# ArduinoUnoShield.net
KiCad netlist of a schematic drawn in Altium Designer
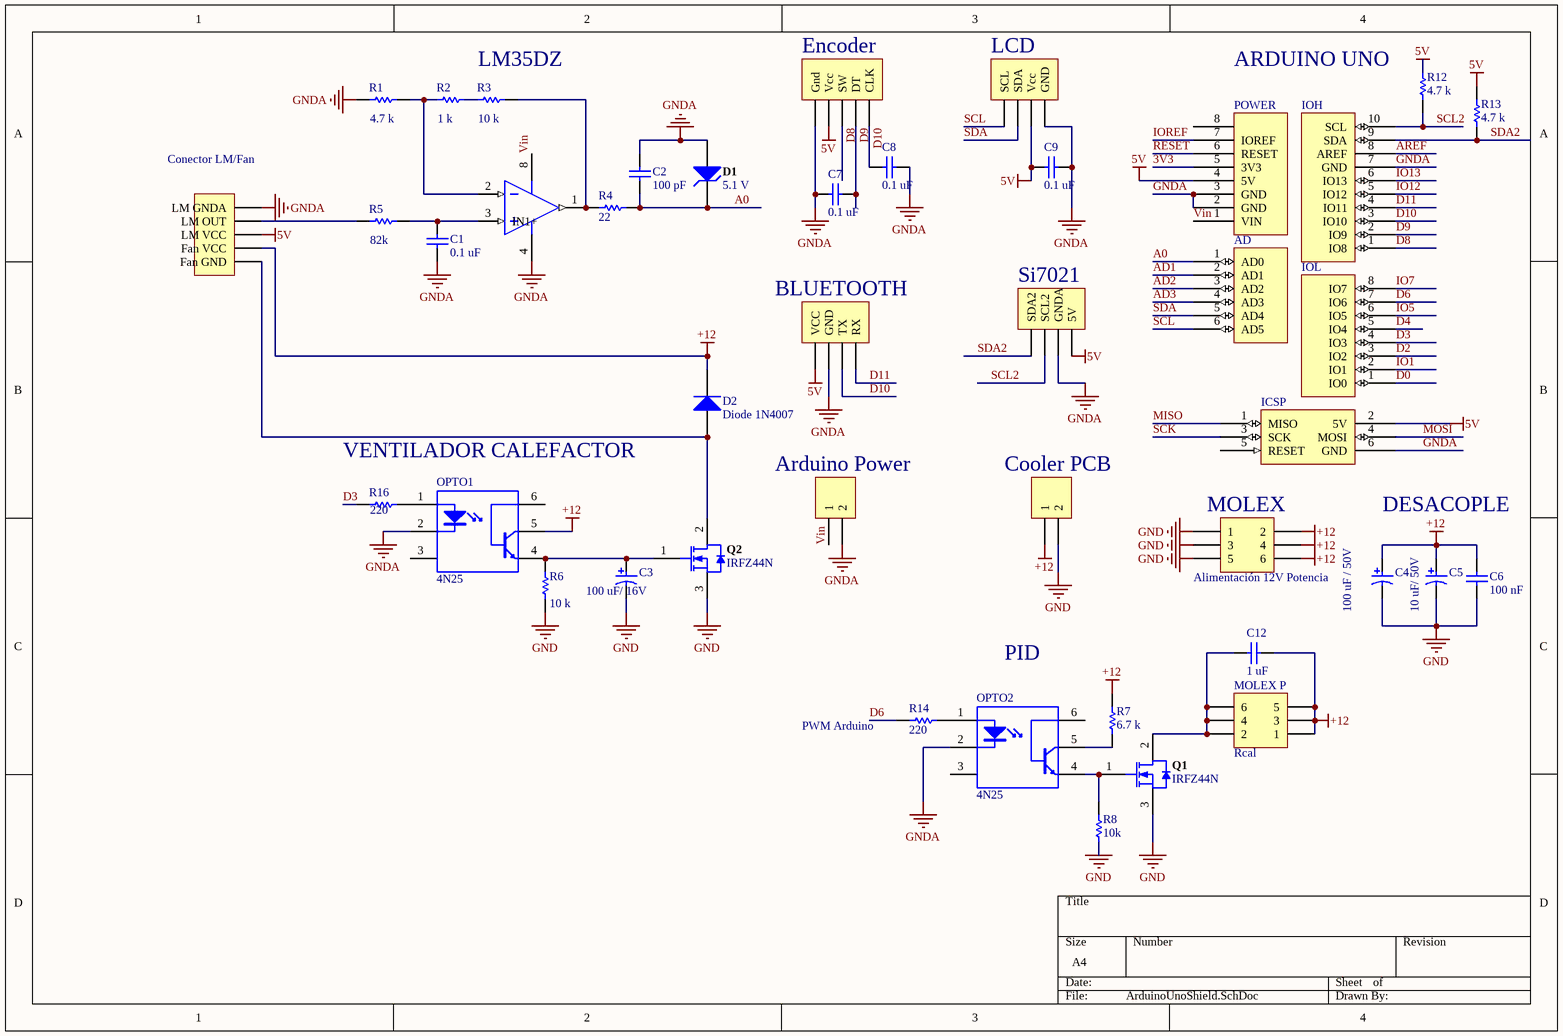
[diagram p0: ArduinoUnoShield.SchDoc]

(export (version "E")
  (design (tool "Eeschema 10.0.6"))
  (components
    (comp (ref "AD")
      (value "AD")
      (footprint "Header:Header 6x1 8.5mm")
      (libsource (lib "Header") (part "AD"))
    )
    (comp (ref "Arduino Power")
      (value "Cooler")
      (footprint "HDR1X2")
      (description "Header, 2-Pin")
      (fields (field (name "PUBLISHER") "Altium Limited"))
      (libsource (lib "Miscellaneous Connectors") (part "Header 2"))
    )
    (comp (ref "BT")
      (value "BLUETOOTH")
      (footprint "HDR1X4")
      (description "Header, 4-Pin")
      (fields (field (name "PUBLISHER") "Altium Limited"))
      (libsource (lib "Miscellaneous Connectors") (part "Header 4"))
    )
    (comp (ref "C1")
      (value "0.1 uF")
      (footprint "KEMT-C315-THT-2")
      (description "Capacitor, Ceramic, 1000 pF, +/-10 %, 100 V, X7R, -55 to 125 degC, 2-Pin THD, RoHS, Bulk")
      (libsource (lib "Altium Content Vault") (part "CAP-NP-2"))
    )
    (comp (ref "C2")
      (value "100 pF")
      (footprint "KEMT-C315-THT-2")
      (description "Capacitor, Ceramic, 1000 pF, +/-10 %, 100 V, X7R, -55 to 125 degC, 2-Pin THD, RoHS, Bulk")
      (libsource (lib "Altium Content Vault") (part "CAP-NP-2"))
    )
    (comp (ref "C3")
      (value "100 uF/ 16V")
      (footprint "CAPPR55-250-1120X630X1220")
      (description "Aluminum Electrolytic Capacitor, 22 uF, +/- 20%, 100 V, -40 to 85 degC, 2-Pin THD, RoHS, Bulk")
      (libsource (lib "Altium Content Vault") (part "CAP-P-2"))
    )
    (comp (ref "C4")
      (value "100 uF / 50V")
      (footprint "CAPPR55-250-1120X630X1220")
      (description "Aluminum Electrolytic Capacitor, 22 uF, +/- 20%, 100 V, -40 to 85 degC, 2-Pin THD, RoHS, Bulk")
      (libsource (lib "Altium Content Vault") (part "CAP-P-2"))
    )
    (comp (ref "C5")
      (value "10 uF/ 50V")
      (footprint "CAPPR55-250-1120X630X1220")
      (description "Aluminum Electrolytic Capacitor, 22 uF, +/- 20%, 100 V, -40 to 85 degC, 2-Pin THD, RoHS, Bulk")
      (libsource (lib "Altium Content Vault") (part "CAP-P-2"))
    )
    (comp (ref "C6")
      (value "100 nF")
      (footprint "KEMT-C315-THT-2")
      (description "Capacitor, Ceramic, 1000 pF, +/-10 %, 100 V, X7R, -55 to 125 degC, 2-Pin THD, RoHS, Bulk")
      (libsource (lib "Altium Content Vault") (part "CAP-NP-2"))
    )
    (comp (ref "C7")
      (value "0.1 uF")
      (footprint "KEMT-C315-THT-2")
      (description "Capacitor, Ceramic, 1000 pF, +/-10 %, 100 V, X7R, -55 to 125 degC, 2-Pin THD, RoHS, Bulk")
      (libsource (lib "Altium Content Vault") (part "CAP-NP-2"))
    )
    (comp (ref "C8")
      (value "0.1 uF")
      (footprint "KEMT-C315-THT-2")
      (description "Capacitor, Ceramic, 1000 pF, +/-10 %, 100 V, X7R, -55 to 125 degC, 2-Pin THD, RoHS, Bulk")
      (libsource (lib "Altium Content Vault") (part "CAP-NP-2"))
    )
    (comp (ref "C9")
      (value "0.1 uF")
      (footprint "KEMT-C315-THT-2")
      (description "Capacitor, Ceramic, 1000 pF, +/-10 %, 100 V, X7R, -55 to 125 degC, 2-Pin THD, RoHS, Bulk")
      (libsource (lib "Altium Content Vault") (part "CAP-NP-2"))
    )
    (comp (ref "C12")
      (value "1 uF")
      (footprint "KEMT-C315-THT-2")
      (description "Capacitor, Ceramic, 1000 pF, +/-10 %, 100 V, X7R, -55 to 125 degC, 2-Pin THD, RoHS, Bulk")
      (libsource (lib "Altium Content Vault") (part "CAP-NP-2"))
    )
    (comp (ref "Conector LM/Fan")
      (value "Header 5")
      (footprint "HDR1X5")
      (description "Header, 5-Pin")
      (fields (field (name "PUBLISHER") "Altium Limited"))
      (libsource (lib "") (part "Header 5_1"))
    )
    (comp (ref "Cooler PCB")
      (value "Cooler")
      (footprint "HDR1X2")
      (description "Header, 2-Pin")
      (fields (field (name "PUBLISHER") "Altium Limited"))
      (libsource (lib "Miscellaneous Connectors") (part "Header 2"))
    )
    (comp (ref "D1")
      (value "5.1 V")
      (footprint "FAIR-DO-41-2_V")
      (description "Zener Diode, 18V, 1W, 5%, -65 to 200 degC, 2-Pin DO-41, Body 2.72 x 5.2 mm, RoHS")
      (fields (field (name "TOLERANCE") "5%") (field (name "MANUFACTURER") "Fairchild Semiconductor"))
      (libsource (lib "Altium Content Vault") (part "FAIR-DZEN-A1K2-2"))
    )
    (comp (ref "D2")
      (value "Diode 1N4007")
      (footprint "DO-41")
      (description "1 Amp General Purpose Rectifier")
      (fields (field (name "PUBLISHER") "Altium Limited"))
      (libsource (lib "Miscellaneous Devices") (part "Diode 1N4007"))
    )
    (comp (ref "Encoder")
      (value "Encoder")
      (footprint "HDR1X5")
      (description "Header, 5-Pin")
      (fields (field (name "PUBLISHER") "Altium Limited"))
      (libsource (lib "Miscellaneous Connectors") (part "Header 5"))
    )
    (comp (ref "ICSP") (value "ICSP") (footprint "ICSP") (libsource (lib "Header") (part "ICSP")))
    (comp (ref "IOH")
      (value "IOH")
      (footprint "Header:Header 10x1 8.5mm")
      (libsource (lib "Header") (part "IOH"))
    )
    (comp (ref "IOL") (value "IOL") (footprint "Header 8x1 8.5mm") (libsource (lib "Header") (part "IOL")))
    (comp (ref "LCD")
      (value "LCD")
      (footprint "HDR1X4")
      (description "Header, 4-Pin")
      (fields (field (name "PUBLISHER") "Altium Limited"))
      (libsource (lib "Miscellaneous Connectors") (part "Header 4"))
    )
    (comp (ref "MOLEX")
      (value "Alimentación 12V Potencia")
      (footprint "HDR2X3")
      (description "Header, 3-Pin, Dual row")
      (fields (field (name "PUBLISHER") "Altium Limited"))
      (libsource (lib "") (part "Header 3X2_1"))
    )
    (comp (ref "MOLEX P")
      (value "Rcal")
      (footprint "HDR2X3")
      (description "Header, 3-Pin, Dual row")
      (fields (field (name "PUBLISHER") "Altium Limited"))
      (libsource (lib "Miscellaneous Connectors") (part "Header 3X2"))
    )
    (comp (ref "OPTO1")
      (value "4N25")
      (footprint "LTST-DIP-6_A")
      (description "Photocoupler - Phototransistor Output, 1500 Vrms, -55 to 100 degC, 6-Pin DIP, RoHS, Tube")
      (fields (field (name "MANUFACTURER") "Vishay"))
      (libsource (lib "Altium Content Vault") (part "OPTO-AKNECB-6"))
    )
    (comp (ref "OPTO2")
      (value "4N25")
      (footprint "LTST-DIP-6_A")
      (description "Photocoupler - Phototransistor Output, 1500 Vrms, -55 to 100 degC, 6-Pin DIP, RoHS, Tube")
      (fields (field (name "MANUFACTURER") "Vishay"))
      (libsource (lib "Altium Content Vault") (part "OPTO-AKNECB-6"))
    )
    (comp (ref "POWER")
      (value "POWER_UNO")
      (footprint "Header 8x1 8.5mm")
      (libsource (lib "Header") (part "POWER_UNO"))
    )
    (comp (ref "Q1")
      (value "IRFZ44N")
      (footprint "VISH-TO-220AB-3_A")
      (description "Power MOSFET, 100 VDS, -55 to 175 degC, 3-Pin TO-220AB, RoHS, Tube")
      (fields (field (name "MANUFACTURER") "Vishay"))
      (libsource (lib "Altium Content Vault") (part "NEMOS-GDS-3"))
    )
    (comp (ref "Q2")
      (value "IRFZ44N")
      (footprint "VISH-TO-220AB-3_A")
      (description "Power MOSFET, 100 VDS, -55 to 175 degC, 3-Pin TO-220AB, RoHS, Tube")
      (fields (field (name "MANUFACTURER") "Vishay"))
      (libsource (lib "Altium Content Vault") (part "NEMOS-GDS-3"))
    )
    (comp (ref "R1")
      (value "4.7 k")
      (footprint "AXIAL-0.3")
      (description "Resistor")
      (fields (field (name "PUBLISHER") "Altium Limited"))
      (libsource (lib "Miscellaneous Devices") (part "Res1"))
    )
    (comp (ref "R2")
      (value "1 k")
      (footprint "AXIAL-0.3")
      (fields (field (name "PUBLISHER") "Altium Limited"))
      (libsource (lib "Miscellaneous Devices") (part "Res1"))
    )
    (comp (ref "R3")
      (value "10 k")
      (footprint "AXIAL-0.3")
      (fields (field (name "PUBLISHER") "Altium Limited"))
      (libsource (lib "Miscellaneous Devices") (part "Res1"))
    )
    (comp (ref "R4")
      (value "22")
      (footprint "AXIAL-0.3")
      (description "Resistor")
      (fields (field (name "PUBLISHER") "Altium Limited"))
      (libsource (lib "Miscellaneous Devices") (part "Res1"))
    )
    (comp (ref "R5")
      (value "82k")
      (footprint "AXIAL-0.3")
      (description "Resistor")
      (fields (field (name "PUBLISHER") "Altium Limited"))
      (libsource (lib "Miscellaneous Devices") (part "Res1"))
    )
    (comp (ref "R6")
      (value "10 k")
      (footprint "AXIAL-0.3")
      (description "Resistor")
      (fields (field (name "PUBLISHER") "Altium Limited"))
      (libsource (lib "Miscellaneous Devices") (part "Res1"))
    )
    (comp (ref "R7")
      (value "6.7 k")
      (footprint "AXIAL-0.3")
      (description "Resistor")
      (fields (field (name "PUBLISHER") "Altium Limited"))
      (libsource (lib "Miscellaneous Devices") (part "Res1"))
    )
    (comp (ref "R8")
      (value "10k")
      (footprint "AXIAL-0.3")
      (description "Resistor")
      (fields (field (name "Comment") "10 k") (field (name "PUBLISHER") "Altium Limited"))
      (libsource (lib "Miscellaneous Devices") (part "Res1"))
    )
    (comp (ref "R12")
      (value "4.7 k")
      (footprint "AXIAL-0.3")
      (description "Resistor")
      (fields (field (name "PUBLISHER") "Altium Limited"))
      (libsource (lib "Miscellaneous Devices") (part "Res1"))
    )
    (comp (ref "R13")
      (value "4.7 k")
      (footprint "AXIAL-0.3")
      (description "Resistor")
      (fields (field (name "PUBLISHER") "Altium Limited"))
      (libsource (lib "Miscellaneous Devices") (part "Res1"))
    )
    (comp (ref "R14")
      (value "220")
      (footprint "AXIAL-0.3")
      (description "Resistor")
      (fields (field (name "PUBLISHER") "Altium Limited"))
      (libsource (lib "Miscellaneous Devices") (part "Res1"))
    )
    (comp (ref "R16")
      (value "220")
      (footprint "AXIAL-0.3")
      (description "Resistor")
      (fields (field (name "PUBLISHER") "Altium Limited"))
      (libsource (lib "Miscellaneous Devices") (part "Res1"))
    )
    (comp (ref "Si7021")
      (value "~")
      (footprint "HDR1X4")
      (description "Header, 4-Pin")
      (fields (field (name "PUBLISHER") "Altium Limited"))
      (libsource (lib "Miscellaneous Connectors") (part "Header 4"))
    )
    (comp (ref "U1")
      (value "~")
      (footprint "ONSC-PDIP-8-626-05")
      (description "Low Voltage, Rail-to-Rail Operational Amplifier, 1.8 to 12 V, -40 to 105 degC, 8-Pin PDIP, Tube")
      (fields (field (name "MANUFACTURER") "On Semiconductor") (field (name "PARTNUMBER") "MC33202P"))
      (libsource (lib "Altium Content Vault") (part "ONSC-LM833_MC3XXXXX_NCV33202-8"))
    )
  )
  (nets
    (net (code "1") (name "+12") (class "Default")
      (node (ref "C12") (pin "1") (pinfunction "1_1") (pintype "passive"))
      (node (ref "C4") (pin "1") (pinfunction "1_1") (pintype "passive"))
      (node (ref "C5") (pin "1") (pinfunction "1_1") (pintype "passive"))
      (node (ref "C6") (pin "2") (pinfunction "2_2") (pintype "passive"))
      (node (ref "Conector LM/Fan") (pin "2") (pinfunction "Fan_VCC_2") (pintype "passive"))
      (node (ref "Cooler PCB") (pin "1") (pinfunction "1_1") (pintype "passive"))
      (node (ref "D2") (pin "2") (pinfunction "K_2") (pintype "passive"))
      (node (ref "MOLEX") (pin "2") (pinfunction "2_2") (pintype "passive"))
      (node (ref "MOLEX") (pin "4") (pinfunction "4_4") (pintype "passive"))
      (node (ref "MOLEX") (pin "6") (pinfunction "6_6") (pintype "passive"))
      (node (ref "MOLEX P") (pin "1") (pinfunction "1_1") (pintype "passive"))
      (node (ref "MOLEX P") (pin "3") (pinfunction "3_3") (pintype "passive"))
      (node (ref "MOLEX P") (pin "5") (pinfunction "5_5") (pintype "passive"))
      (node (ref "OPTO1") (pin "5") (pinfunction "C_5") (pintype "passive"))
      (node (ref "R7") (pin "2") (pinfunction "2_2") (pintype "passive"))
    )
    (net (code "2") (name "/3V3") (class "Default")
      (node (ref "POWER") (pin "5") (pinfunction "3V3_5") (pintype "power_in"))
    )
    (net (code "4") (name "/A0") (class "Default")
      (node (ref "AD") (pin "1") (pinfunction "AD0_1") (pintype "bidirectional"))
      (node (ref "C2") (pin "2") (pinfunction "2_2") (pintype "passive"))
      (node (ref "D1") (pin "2") (pinfunction "K_2") (pintype "passive"))
      (node (ref "R4") (pin "1") (pinfunction "1_1") (pintype "passive"))
    )
    (net (code "5") (name "/AD1") (class "Default")
      (node (ref "AD") (pin "2") (pinfunction "AD1_2") (pintype "bidirectional"))
    )
    (net (code "6") (name "/AD2") (class "Default")
      (node (ref "AD") (pin "3") (pinfunction "AD2_3") (pintype "bidirectional"))
    )
    (net (code "7") (name "/AD3") (class "Default")
      (node (ref "AD") (pin "4") (pinfunction "AD3_4") (pintype "bidirectional"))
    )
    (net (code "8") (name "/AREF") (class "Default")
      (node (ref "IOH") (pin "8") (pinfunction "AREF_8") (pintype "passive"))
    )
    (net (code "9") (name "/D0") (class "Default")
      (node (ref "IOL") (pin "1") (pinfunction "IO0_1") (pintype "bidirectional"))
    )
    (net (code "10") (name "/D2") (class "Default")
      (node (ref "IOL") (pin "3") (pinfunction "IO2_3") (pintype "bidirectional"))
    )
    (net (code "11") (name "/D3") (class "Default")
      (node (ref "IOL") (pin "4") (pinfunction "IO3_4") (pintype "bidirectional"))
      (node (ref "R16") (pin "1") (pinfunction "1_1") (pintype "passive"))
    )
    (net (code "12") (name "/D4") (class "Default")
      (node (ref "IOL") (pin "5") (pinfunction "IO4_5") (pintype "bidirectional"))
    )
    (net (code "13") (name "/D6") (class "Default")
      (node (ref "IOL") (pin "7") (pinfunction "IO6_7") (pintype "bidirectional"))
      (node (ref "R14") (pin "2") (pinfunction "2_2") (pintype "passive"))
    )
    (net (code "14") (name "/D8") (class "Default")
      (node (ref "Encoder") (pin "3") (pinfunction "SW_3") (pintype "passive"))
      (node (ref "IOH") (pin "1") (pinfunction "IO8_1") (pintype "bidirectional"))
    )
    (net (code "15") (name "/D9") (class "Default")
      (node (ref "C7") (pin "2") (pinfunction "2_2") (pintype "passive"))
      (node (ref "Encoder") (pin "4") (pinfunction "DT_4") (pintype "passive"))
      (node (ref "IOH") (pin "2") (pinfunction "IO9_2") (pintype "bidirectional"))
    )
    (net (code "16") (name "/D10") (class "Default")
      (node (ref "BT") (pin "3") (pinfunction "TX_3") (pintype "passive"))
      (node (ref "C8") (pin "1") (pinfunction "1_1") (pintype "passive"))
      (node (ref "Encoder") (pin "5") (pinfunction "CLK_5") (pintype "passive"))
      (node (ref "IOH") (pin "3") (pinfunction "IO10_3") (pintype "bidirectional"))
    )
    (net (code "17") (name "/D11") (class "Default")
      (node (ref "BT") (pin "4") (pinfunction "RX_4") (pintype "passive"))
      (node (ref "IOH") (pin "4") (pinfunction "IO11_4") (pintype "bidirectional"))
    )
    (net (code "18") (name "/IO1") (class "Default")
      (node (ref "IOL") (pin "2") (pinfunction "IO1_2") (pintype "bidirectional"))
    )
    (net (code "19") (name "/IO5") (class "Default")
      (node (ref "IOL") (pin "6") (pinfunction "IO5_6") (pintype "bidirectional"))
    )
    (net (code "20") (name "/IO7") (class "Default")
      (node (ref "IOL") (pin "8") (pinfunction "IO7_8") (pintype "bidirectional"))
    )
    (net (code "21") (name "/IO12") (class "Default")
      (node (ref "IOH") (pin "5") (pinfunction "IO12_5") (pintype "bidirectional"))
    )
    (net (code "22") (name "/IO13") (class "Default")
      (node (ref "IOH") (pin "6") (pinfunction "IO13_6") (pintype "bidirectional"))
    )
    (net (code "23") (name "/IOREF") (class "Default")
      (node (ref "POWER") (pin "7") (pinfunction "IOREF_7") (pintype "power_in"))
    )
    (net (code "24") (name "/MISO") (class "Default")
      (node (ref "ICSP") (pin "1") (pinfunction "MISO_1") (pintype "bidirectional"))
    )
    (net (code "25") (name "/MOSI") (class "Default")
      (node (ref "ICSP") (pin "4") (pinfunction "MOSI_4") (pintype "bidirectional"))
    )
    (net (code "26") (name "/RESET") (class "Default")
      (node (ref "POWER") (pin "6") (pinfunction "RESET_6") (pintype "passive"))
    )
    (net (code "27") (name "/SCK") (class "Default")
      (node (ref "ICSP") (pin "3") (pinfunction "SCK_3") (pintype "bidirectional"))
    )
    (net (code "28") (name "/SCL") (class "Default")
      (node (ref "AD") (pin "6") (pinfunction "AD5_6") (pintype "bidirectional"))
      (node (ref "LCD") (pin "1") (pinfunction "VCC_1") (pintype "passive"))
    )
    (net (code "29") (name "/SCL2") (class "Default")
      (node (ref "IOH") (pin "10") (pinfunction "SCL_10") (pintype "bidirectional"))
      (node (ref "R12") (pin "1") (pinfunction "1_1") (pintype "passive"))
      (node (ref "Si7021") (pin "2") (pinfunction "GND_2") (pintype "passive"))
    )
    (net (code "30") (name "/SDA") (class "Default")
      (node (ref "AD") (pin "5") (pinfunction "AD4_5") (pintype "bidirectional"))
      (node (ref "LCD") (pin "2") (pinfunction "GND_2") (pintype "passive"))
    )
    (net (code "31") (name "/SDA2") (class "Default")
      (node (ref "IOH") (pin "9") (pinfunction "SDA_9") (pintype "bidirectional"))
      (node (ref "R13") (pin "1") (pinfunction "1_1") (pintype "passive"))
      (node (ref "Si7021") (pin "1") (pinfunction "VCC_1") (pintype "passive"))
    )
    (net (code "32") (name "/Vin") (class "Default")
      (node (ref "Arduino Power") (pin "1") (pinfunction "1_1") (pintype "passive"))
      (node (ref "POWER") (pin "1") (pinfunction "VIN_1") (pintype "power_in"))
      (node (ref "U1") (pin "8") (pinfunction "VCC_8") (pintype "power_in"))
    )
    (net (code "33") (name "5V") (class "Default")
      (node (ref "BT") (pin "1") (pinfunction "VCC_1") (pintype "passive"))
      (node (ref "C9") (pin "2") (pinfunction "2_2") (pintype "passive"))
      (node (ref "Conector LM/Fan") (pin "4") (pinfunction "LM_VCC_4") (pintype "passive"))
      (node (ref "Encoder") (pin "2") (pinfunction "Vcc_2") (pintype "passive"))
      (node (ref "ICSP") (pin "2") (pinfunction "5V_2") (pintype "power_in"))
      (node (ref "LCD") (pin "3") (pinfunction "TX_3") (pintype "passive"))
      (node (ref "POWER") (pin "4") (pinfunction "5V_4") (pintype "power_in"))
      (node (ref "R12") (pin "2") (pinfunction "2_2") (pintype "passive"))
      (node (ref "R13") (pin "2") (pinfunction "2_2") (pintype "passive"))
      (node (ref "Si7021") (pin "4") (pinfunction "RX_4") (pintype "passive"))
    )
    (net (code "34") (name "GND") (class "Default")
      (node (ref "C3") (pin "2") (pinfunction "2_2") (pintype "passive"))
      (node (ref "C4") (pin "2") (pinfunction "2_2") (pintype "passive"))
      (node (ref "C5") (pin "2") (pinfunction "2_2") (pintype "passive"))
      (node (ref "C6") (pin "1") (pinfunction "1_1") (pintype "passive"))
      (node (ref "Cooler PCB") (pin "2") (pinfunction "2_2") (pintype "passive"))
      (node (ref "MOLEX") (pin "1") (pinfunction "1_1") (pintype "passive"))
      (node (ref "MOLEX") (pin "3") (pinfunction "3_3") (pintype "passive"))
      (node (ref "MOLEX") (pin "5") (pinfunction "5_5") (pintype "passive"))
      (node (ref "Q1") (pin "3") (pinfunction "S_3") (pintype "passive"))
      (node (ref "Q2") (pin "3") (pinfunction "S_3") (pintype "passive"))
      (node (ref "R6") (pin "2") (pinfunction "2_2") (pintype "passive"))
      (node (ref "R8") (pin "1") (pinfunction "1_1") (pintype "passive"))
    )
    (net (code "35") (name "GNDA") (class "Default")
      (node (ref "Arduino Power") (pin "2") (pinfunction "2_2") (pintype "passive"))
      (node (ref "BT") (pin "2") (pinfunction "GND_2") (pintype "passive"))
      (node (ref "C1") (pin "1") (pinfunction "1_1") (pintype "passive"))
      (node (ref "C2") (pin "1") (pinfunction "1_1") (pintype "passive"))
      (node (ref "C7") (pin "1") (pinfunction "1_1") (pintype "passive"))
      (node (ref "C8") (pin "2") (pinfunction "2_2") (pintype "passive"))
      (node (ref "C9") (pin "1") (pinfunction "1_1") (pintype "passive"))
      (node (ref "Conector LM/Fan") (pin "5") (pinfunction "LM_GNDA_5") (pintype "passive"))
      (node (ref "D1") (pin "1") (pinfunction "A_1") (pintype "passive"))
      (node (ref "Encoder") (pin "1") (pinfunction "Gnd_1") (pintype "passive"))
      (node (ref "ICSP") (pin "6") (pinfunction "GND_6") (pintype "power_in"))
      (node (ref "IOH") (pin "7") (pinfunction "GND_7") (pintype "power_in"))
      (node (ref "LCD") (pin "4") (pinfunction "RX_4") (pintype "passive"))
      (node (ref "OPTO1") (pin "2") (pinfunction "C_2") (pintype "passive"))
      (node (ref "OPTO2") (pin "2") (pinfunction "C_2") (pintype "passive"))
      (node (ref "POWER") (pin "2") (pinfunction "GND_2") (pintype "power_in"))
      (node (ref "POWER") (pin "3") (pinfunction "GND_3") (pintype "power_in"))
      (node (ref "R1") (pin "1") (pinfunction "1_1") (pintype "passive"))
      (node (ref "Si7021") (pin "3") (pinfunction "TX_3") (pintype "passive"))
      (node (ref "U1") (pin "4") (pinfunction "VEE_4") (pintype "power_in"))
    )
    (net (code "36") (name "Net-(Conector LM/Fan-Fan_GND)") (class "Default")
      (node (ref "Conector LM/Fan") (pin "1") (pinfunction "Fan_GND_1") (pintype "passive"))
      (node (ref "D2") (pin "1") (pinfunction "A_1") (pintype "passive"))
      (node (ref "Q2") (pin "2") (pinfunction "D_2") (pintype "passive"))
    )
    (net (code "37") (name "Net-(Conector LM/Fan-LM_OUT)") (class "Default")
      (node (ref "Conector LM/Fan") (pin "3") (pinfunction "LM_OUT_3") (pintype "passive"))
      (node (ref "R5") (pin "1") (pinfunction "1_1") (pintype "passive"))
    )
    (net (code "38") (name "Net-(OPTO1-A)") (class "Default")
      (node (ref "OPTO1") (pin "1") (pinfunction "A_1") (pintype "passive"))
      (node (ref "R16") (pin "2") (pinfunction "2_2") (pintype "passive"))
    )
    (net (code "39") (name "Net-(OPTO1-E)") (class "Default")
      (node (ref "C3") (pin "1") (pinfunction "1_1") (pintype "passive"))
      (node (ref "OPTO1") (pin "4") (pinfunction "E_4") (pintype "passive"))
      (node (ref "Q2") (pin "1") (pinfunction "G_1") (pintype "passive"))
      (node (ref "R6") (pin "1") (pinfunction "1_1") (pintype "passive"))
    )
    (net (code "40") (name "Net-(OPTO2-A)") (class "Default")
      (node (ref "OPTO2") (pin "1") (pinfunction "A_1") (pintype "passive"))
      (node (ref "R14") (pin "1") (pinfunction "1_1") (pintype "passive"))
    )
    (net (code "41") (name "Net-(OPTO2-C-Pad5)") (class "Default")
      (node (ref "OPTO2") (pin "5") (pinfunction "C_5") (pintype "passive"))
      (node (ref "R7") (pin "1") (pinfunction "1_1") (pintype "passive"))
    )
    (net (code "42") (name "Net-(OPTO2-E)") (class "Default")
      (node (ref "OPTO2") (pin "4") (pinfunction "E_4") (pintype "passive"))
      (node (ref "Q1") (pin "1") (pinfunction "G_1") (pintype "passive"))
      (node (ref "R8") (pin "2") (pinfunction "2_2") (pintype "passive"))
    )
    (net (code "43") (name "Net-(Q1-D)") (class "Default")
      (node (ref "C12") (pin "2") (pinfunction "2_2") (pintype "passive"))
      (node (ref "MOLEX P") (pin "2") (pinfunction "2_2") (pintype "passive"))
      (node (ref "MOLEX P") (pin "4") (pinfunction "4_4") (pintype "passive"))
      (node (ref "MOLEX P") (pin "6") (pinfunction "6_6") (pintype "passive"))
      (node (ref "Q1") (pin "2") (pinfunction "D_2") (pintype "passive"))
    )
    (net (code "44") (name "Net-(R2-Pad2)") (class "Default")
      (node (ref "R2") (pin "2") (pinfunction "2_2") (pintype "passive"))
      (node (ref "R3") (pin "1") (pinfunction "1_1") (pintype "passive"))
    )
    (net (code "45") (name "Net-(U1A-IN1+)") (class "Default")
      (node (ref "C1") (pin "2") (pinfunction "2_2") (pintype "passive"))
      (node (ref "R5") (pin "2") (pinfunction "2_2") (pintype "passive"))
      (node (ref "U1") (pin "3") (pinfunction "IN1+_3") (pintype "input"))
    )
    (net (code "46") (name "Net-(U1A-IN1-)") (class "Default")
      (node (ref "R1") (pin "2") (pinfunction "2_2") (pintype "passive"))
      (node (ref "R2") (pin "1") (pinfunction "1_1") (pintype "passive"))
      (node (ref "U1") (pin "2") (pinfunction "IN1-_2") (pintype "input"))
    )
    (net (code "47") (name "Net-(U1A-OUT1)") (class "Default")
      (node (ref "R3") (pin "2") (pinfunction "2_2") (pintype "passive"))
      (node (ref "R4") (pin "2") (pinfunction "2_2") (pintype "passive"))
      (node (ref "U1") (pin "1") (pinfunction "OUT1_1") (pintype "output"))
    )
    (net (code "48") (name "unconnected-(ICSP-RESET-Pad5)") (class "Default")
      (node (ref "ICSP") (pin "5") (pinfunction "RESET_5") (pintype "input"))
    )
    (net (code "49") (name "unconnected-(OPTO1-B-Pad6)") (class "Default")
      (node (ref "OPTO1") (pin "6") (pinfunction "B_6") (pintype "passive"))
    )
    (net (code "50") (name "unconnected-(OPTO1-NC-Pad3)") (class "Default")
      (node (ref "OPTO1") (pin "3") (pinfunction "NC_3") (pintype "passive"))
    )
    (net (code "51") (name "unconnected-(OPTO2-B-Pad6)") (class "Default")
      (node (ref "OPTO2") (pin "6") (pinfunction "B_6") (pintype "passive"))
    )
    (net (code "52") (name "unconnected-(OPTO2-NC-Pad3)") (class "Default")
      (node (ref "OPTO2") (pin "3") (pinfunction "NC_3") (pintype "passive"))
    )
    (net (code "53") (name "unconnected-(POWER-Pad8)") (class "Default")
      (node (ref "POWER") (pin "8") (pintype "passive"))
    )
  )
)
